# SB_schematic.net
KiCad netlist of a schematic drawn in Altium Designer
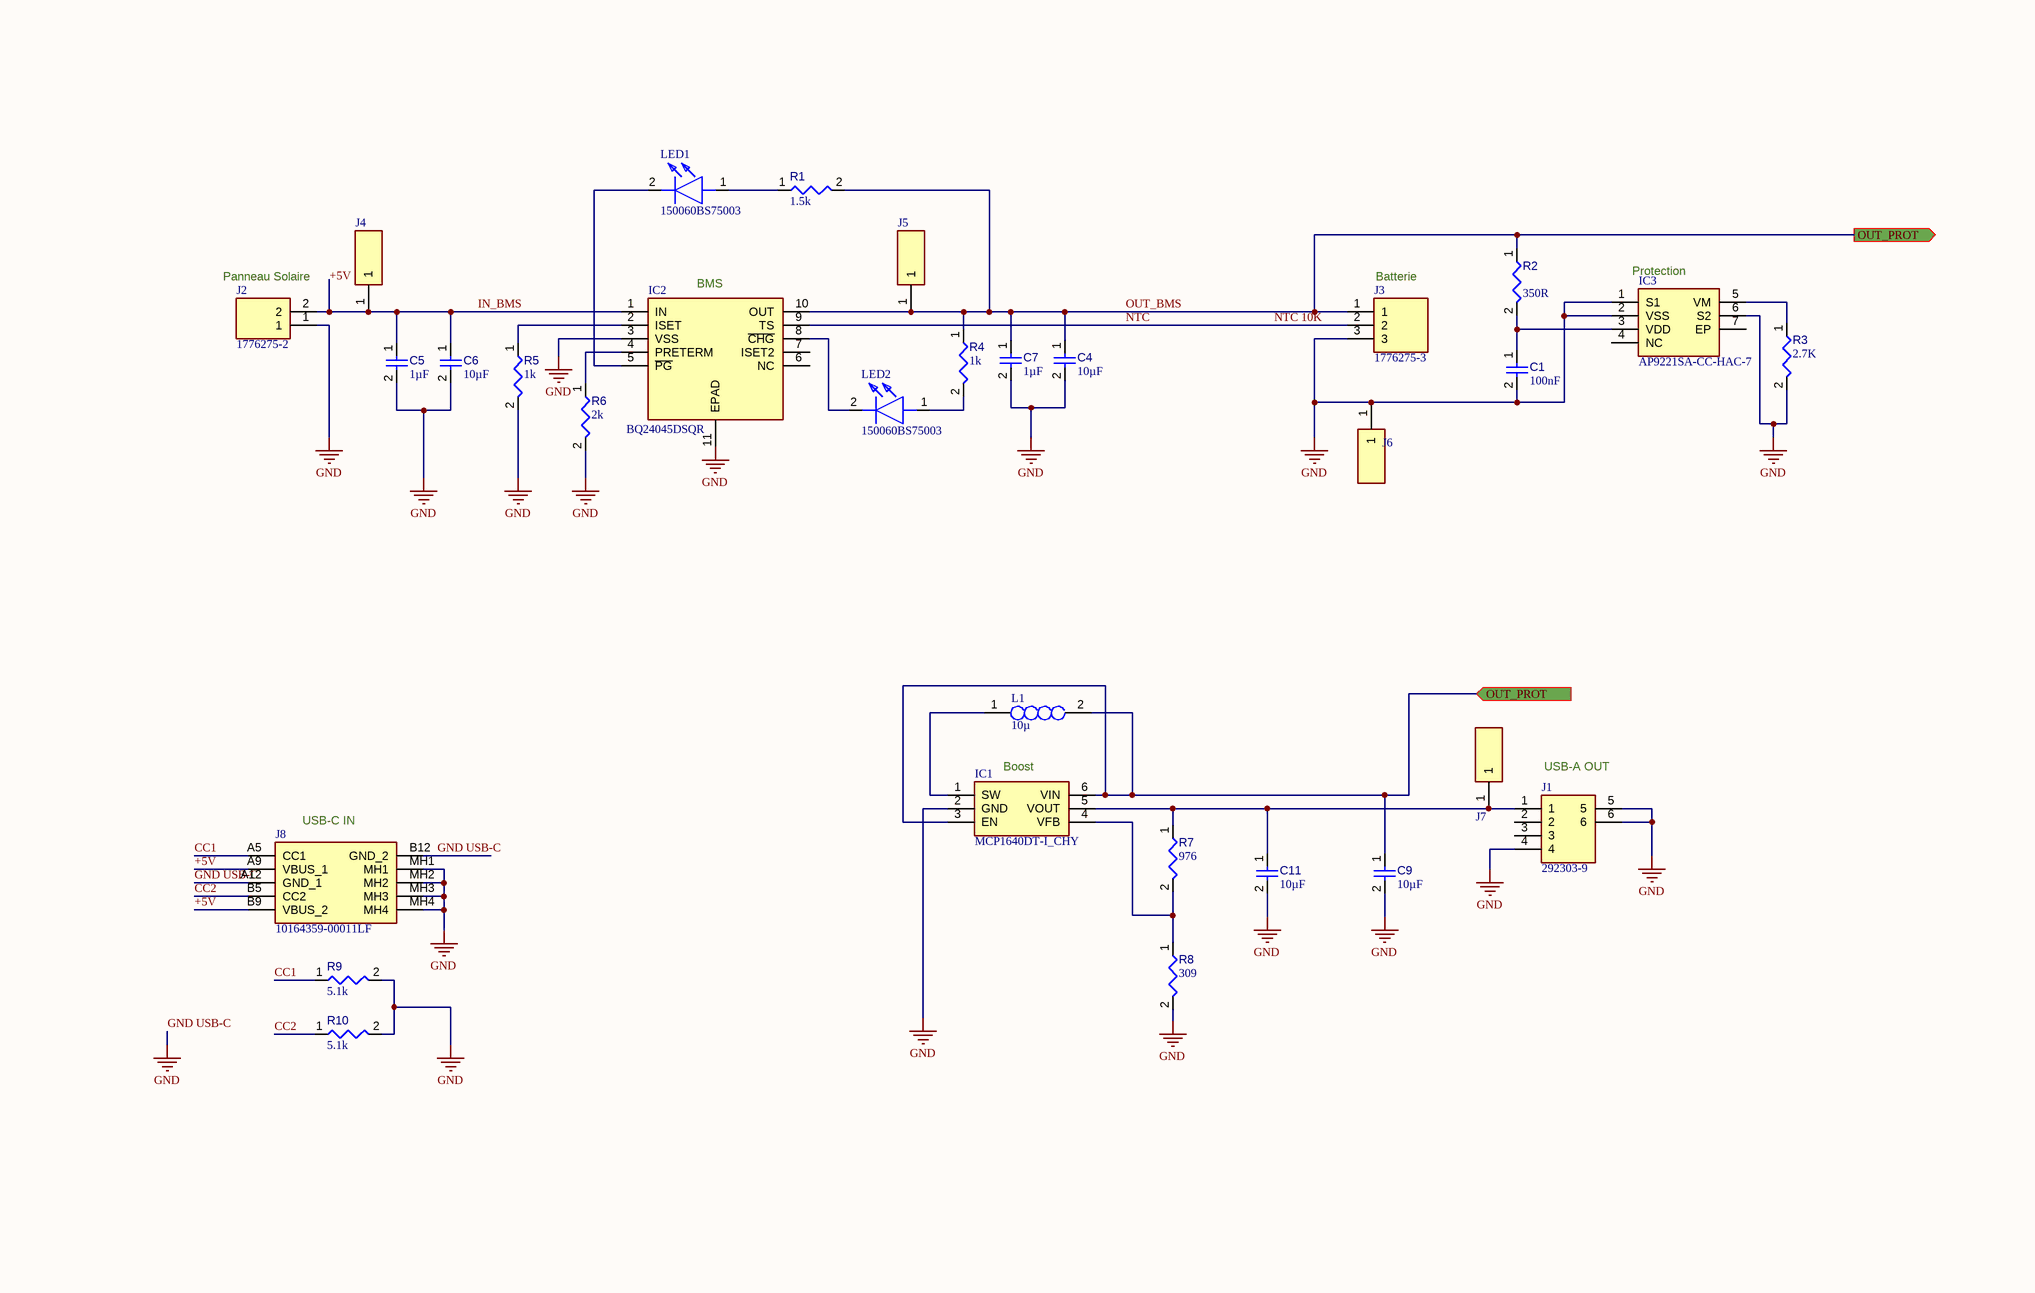
[diagram p0: SB_schematic.SchDoc]

(export (version "E")
  (design (tool "Eeschema 10.0.6"))
  (components
    (comp (ref "C1")
      (value "100nF")
      (footprint "CAPC1608X90X40LL10T20")
      (description "Chip Capacitor, 1 uF, +/- 10%, 25 V, 0603 (1608 Metric)")
      (fields (field (name "TOLERANCE") "10%") (field (name "Comment") "Capacitor 100 nF"))
      (libsource (lib "Haute Ecole de La Province de Liège") (part "CAP-NP-2"))
    )
    (comp (ref "C4")
      (value "10µF")
      (footprint "CAPC1608X90X40LL10T20")
      (description "Chip Capacitor, 1 uF, +/- 10%, 25 V, 0603 (1608 Metric)")
      (fields (field (name "TOLERANCE") "10%") (field (name "Comment") "Capacitor 10 uF"))
      (libsource (lib "Haute Ecole de La Province de Liège") (part "CAP-NP-2"))
    )
    (comp (ref "C5")
      (value "1µF")
      (footprint "CAPC1608X90X40LL10T20")
      (description "Chip Capacitor, 1 uF, +/- 10%, 25 V, 0603 (1608 Metric)")
      (fields (field (name "TOLERANCE") "10%") (field (name "Comment") "Capacitor 1 uF +/- 10% 25 V 0603"))
      (libsource (lib "Haute Ecole de La Province de Liège") (part "CAP-NP-2"))
    )
    (comp (ref "C6")
      (value "10µF")
      (footprint "CAPC1608X90X40LL10T20")
      (description "Chip Capacitor, 10 uF,")
      (fields (field (name "TOLERANCE") "10%") (field (name "Comment") "Capacitor 10 uF"))
      (libsource (lib "Haute Ecole de La Province de Liège") (part "CAP-NP-2"))
    )
    (comp (ref "C7")
      (value "1µF")
      (footprint "CAPC1608X90X40LL10T20")
      (description "Chip Capacitor, 1 uF, +/- 10%, 25 V, 0603 (1608 Metric)")
      (fields (field (name "TOLERANCE") "10%") (field (name "Comment") "Capacitor 1 uF +/- 10% 25 V 0603"))
      (libsource (lib "Haute Ecole de La Province de Liège") (part "CAP-NP-2"))
    )
    (comp (ref "C9")
      (value "10µF")
      (footprint "CAPC1608X90X40LL10T20")
      (description "Chip Capacitor, 1 uF, +/- 10%, 25 V, 0603 (1608 Metric)")
      (fields (field (name "TOLERANCE") "10%") (field (name "Comment") "Capacitor 10 uF"))
      (libsource (lib "Haute Ecole de La Province de Liège") (part "CAP-NP-2"))
    )
    (comp (ref "C11")
      (value "10µF")
      (footprint "CAPC1608X90X40LL10T20")
      (description "Chip Capacitor, 1 uF, +/- 10%, 25 V, 0603 (1608 Metric)")
      (fields (field (name "TOLERANCE") "10%") (field (name "Comment") "Capacitor 10 uF"))
      (libsource (lib "Haute Ecole de La Province de Liège") (part "CAP-NP-2"))
    )
    (comp (ref "IC1")
      (value "MCP1640DT-I_CHY")
      (footprint "SamacSys:SOT95P270X145-6N")
      (description "Integrated Circuit")
      (fields
        (field (name "MANUFACTURER_PART_NUMBER") "MCP1640DT-I/CHY")
        (field (name "MOUSER PART NUMBER") "579-MCP1640DT-I/CHY")
      )
      (libsource (lib "*") (part "MCP1640DT-I_CHY"))
    )
    (comp (ref "IC2")
      (value "BQ24045DSQR")
      (footprint "SamacSys:SON40P200X200X80-11N")
      (description "Integrated Circuit")
      (fields (field (name "MOUSER PART NUMBER") "595-BQ24045DSQR"))
      (libsource (lib "*") (part "BQ24045DSQR"))
    )
    (comp (ref "IC3")
      (value "AP9221SA-CC-HAC-7")
      (footprint "SamacSys:AP9221SACCHAC7")
      (description "Integrated Circuit")
      (fields (field (name "MOUSER PART NUMBER") "621-AP9221SA-CCHAC-7"))
      (libsource (lib "*") (part "AP9221SA-CC-HAC-7"))
    )
    (comp (ref "J1")
      (value "292303-9")
      (footprint "SamacSys:2923039")
      (description "Connector")
      (fields (field (name "MOUSER PART NUMBER") "571-292303-9"))
      (libsource (lib "*") (part "292303-9"))
    )
    (comp (ref "J2")
      (value "1776275-2")
      (footprint "SamacSys:17762752")
      (description "Connector")
      (fields (field (name "MOUSER PART NUMBER") "571-1776275-2"))
      (libsource (lib "*") (part "1776275-2"))
    )
    (comp (ref "J3")
      (value "1776275-3")
      (footprint "SamacSys:17762753")
      (description "Connector")
      (fields (field (name "MOUSER PART NUMBER") "571-1776275-3"))
      (libsource (lib "*") (part "1776275-3"))
    )
    (comp (ref "J4")
      (value "050_LT_B2")
      (footprint "SamacSys:050LTB2")
      (description "Connector")
      (fields (field (name "MANUFACTURER_PART_NUMBER") "050/LT/B2"))
      (libsource (lib "*") (part "050_LT_B2"))
    )
    (comp (ref "J5")
      (value "050_LT_B2")
      (footprint "SamacSys:050LTB2")
      (description "Connector")
      (fields (field (name "MANUFACTURER_PART_NUMBER") "050/LT/B2"))
      (libsource (lib "*") (part "050_LT_B2"))
    )
    (comp (ref "J6")
      (value "050_LT_B2")
      (footprint "SamacSys:050LTB2")
      (description "Connector")
      (fields (field (name "MANUFACTURER_PART_NUMBER") "050/LT/B2"))
      (libsource (lib "") (part "050_LT_B2_1"))
    )
    (comp (ref "J7")
      (value "050_LT_B2")
      (footprint "SamacSys:050LTB2")
      (description "Connector")
      (fields (field (name "MANUFACTURER_PART_NUMBER") "050/LT/B2"))
      (libsource (lib "*") (part "050_LT_B2"))
    )
    (comp (ref "J8")
      (value "10164359-00011LF")
      (footprint "SamacSys:1016435900011LF")
      (description "Connector")
      (fields (field (name "MOUSER PART NUMBER") "649-10164359-00011LF"))
      (libsource (lib "*") (part "10164359-00011LF"))
    )
    (comp (ref "L1")
      (value "10µ")
      (footprint "SamacSys:74477710")
      (description "Inductor")
      (fields
        (field (name "MANUFACTURER_PART_NUMBER") "74477710")
        (field (name "MOUSER PART NUMBER") "710-74477710")
      )
      (libsource (lib "*") (part "74477710"))
    )
    (comp (ref "LED1")
      (value "150060BS75003")
      (footprint "SamacSys:150060BS75003")
      (description "LED")
      (fields (field (name "MOUSER PART NUMBER") "710-150060BS75003"))
      (libsource (lib "*") (part "150060BS75003"))
    )
    (comp (ref "LED2")
      (value "150060BS75003")
      (footprint "SamacSys:150060BS75003")
      (description "LED")
      (fields (field (name "MOUSER PART NUMBER") "710-150060BS75003"))
      (libsource (lib "*") (part "150060BS75003"))
    )
    (comp (ref "R1")
      (value "1.5k")
      (footprint "RESC0603(1608)_L")
      (description "Chip Resistor, 120 Ohms, +/-5 %, 0.1 W, -55 to 155 degC, 0603")
      (fields (field (name "POWER") "100mW") (field (name "TOLERANCE") "5%"))
      (libsource (lib "Haute Ecole de La Province de Liège") (part "RES-2"))
    )
    (comp (ref "R2")
      (value "350R")
      (footprint "RESC0603(1608)_L")
      (description "Chip Resistor, 120 Ohms, +/-5 %, 0.1 W, -55 to 155 degC, 0603")
      (fields (field (name "POWER") "100mW") (field (name "TOLERANCE") "5%"))
      (libsource (lib "Haute Ecole de La Province de Liège") (part "RES-2"))
    )
    (comp (ref "R3")
      (value "2.7K")
      (footprint "RESC0603(1608)_L")
      (description "Chip Resistor, 120 Ohms, +/-5 %, 0.1 W, -55 to 155 degC, 0603")
      (fields (field (name "POWER") "100mW") (field (name "TOLERANCE") "5%"))
      (libsource (lib "Haute Ecole de La Province de Liège") (part "RES-2"))
    )
    (comp (ref "R4")
      (value "1k")
      (footprint "RESC0603(1608)_L")
      (description "Chip Resistor, 120 Ohms, +/-5 %, 0.1 W, -55 to 155 degC, 0603")
      (fields (field (name "POWER") "100mW") (field (name "TOLERANCE") "5%"))
      (libsource (lib "Haute Ecole de La Province de Liège") (part "RES-2"))
    )
    (comp (ref "R5")
      (value "1k")
      (footprint "RESC0603(1608)_L")
      (description "Chip Resistor, 120 Ohms, +/-5 %, 0.1 W, -55 to 155 degC, 0603")
      (fields (field (name "POWER") "100mW") (field (name "TOLERANCE") "5%"))
      (libsource (lib "Haute Ecole de La Province de Liège") (part "RES-2"))
    )
    (comp (ref "R6")
      (value "2k")
      (footprint "RESC0603(1608)_L")
      (description "Chip Resistor, 120 Ohms, +/-5 %, 0.1 W, -55 to 155 degC, 0603")
      (fields (field (name "POWER") "100mW") (field (name "TOLERANCE") "5%"))
      (libsource (lib "Haute Ecole de La Province de Liège") (part "RES-2"))
    )
    (comp (ref "R7")
      (value "976")
      (footprint "RESC0603(1608)_L")
      (description "Chip Resistor, 120 Ohms, +/-5 %, 0.1 W, -55 to 155 degC, 0603")
      (fields (field (name "POWER") "100mW") (field (name "TOLERANCE") "5%"))
      (libsource (lib "Haute Ecole de La Province de Liège") (part "RES-2"))
    )
    (comp (ref "R8")
      (value "309")
      (footprint "RESC0603(1608)_L")
      (description "Chip Resistor, 120 Ohms, +/-5 %, 0.1 W, -55 to 155 degC, 0603")
      (fields (field (name "POWER") "100mW") (field (name "TOLERANCE") "5%"))
      (libsource (lib "Haute Ecole de La Province de Liège") (part "RES-2"))
    )
    (comp (ref "R9")
      (value "5.1k")
      (footprint "RESC0603(1608)_L")
      (description "Chip Resistor, 120 Ohms, +/-5 %, 0.1 W, -55 to 155 degC, 0603")
      (fields (field (name "POWER") "100mW") (field (name "TOLERANCE") "5%"))
      (libsource (lib "Haute Ecole de La Province de Liège") (part "RES-2"))
    )
    (comp (ref "R10")
      (value "5.1k")
      (footprint "RESC0603(1608)_L")
      (description "Chip Resistor, 120 Ohms, +/-5 %, 0.1 W, -55 to 155 degC, 0603")
      (fields (field (name "POWER") "100mW") (field (name "TOLERANCE") "5%"))
      (libsource (lib "Haute Ecole de La Province de Liège") (part "RES-2"))
    )
  )
  (nets
    (net (code "1") (name "/+5V") (class "Default")
      (node (ref "C5") (pin "1") (pinfunction "1_1") (pintype "passive"))
      (node (ref "C6") (pin "1") (pinfunction "1_1") (pintype "passive"))
      (node (ref "IC2") (pin "1") (pinfunction "IN_1") (pintype "passive"))
      (node (ref "J2") (pin "2") (pinfunction "2_2") (pintype "passive"))
      (node (ref "J4") (pin "1") (pinfunction "1_1") (pintype "passive"))
      (node (ref "J8") (pin "A9") (pinfunction "VBUS_1_A9") (pintype "passive"))
      (node (ref "J8") (pin "B9") (pinfunction "VBUS_2_B9") (pintype "passive"))
    )
    (net (code "2") (name "/CC1") (class "Default")
      (node (ref "J8") (pin "A5") (pinfunction "CC1_A5") (pintype "passive"))
      (node (ref "R9") (pin "1") (pinfunction "1_1") (pintype "passive"))
    )
    (net (code "3") (name "/CC2") (class "Default")
      (node (ref "J8") (pin "B5") (pinfunction "CC2_B5") (pintype "passive"))
      (node (ref "R10") (pin "1") (pinfunction "1_1") (pintype "passive"))
    )
    (net (code "4") (name "/NTC") (class "Default")
      (node (ref "IC2") (pin "9") (pinfunction "TS_9") (pintype "passive"))
      (node (ref "J3") (pin "2") (pinfunction "2_2") (pintype "passive"))
    )
    (net (code "5") (name "/OUT_BMS") (class "Default")
      (node (ref "C4") (pin "1") (pinfunction "1_1") (pintype "passive"))
      (node (ref "C7") (pin "1") (pinfunction "1_1") (pintype "passive"))
      (node (ref "C9") (pin "1") (pinfunction "1_1") (pintype "passive"))
      (node (ref "IC1") (pin "3") (pinfunction "EN_3") (pintype "passive"))
      (node (ref "IC1") (pin "6") (pinfunction "VIN_6") (pintype "passive"))
      (node (ref "IC2") (pin "10") (pinfunction "OUT_10") (pintype "passive"))
      (node (ref "J3") (pin "1") (pinfunction "1_1") (pintype "passive"))
      (node (ref "J5") (pin "1") (pinfunction "1_1") (pintype "passive"))
      (node (ref "L1") (pin "2") (pinfunction "2_2") (pintype "passive"))
      (node (ref "R1") (pin "2") (pinfunction "2_2") (pintype "passive"))
      (node (ref "R2") (pin "1") (pinfunction "1_1") (pintype "passive"))
      (node (ref "R4") (pin "1") (pinfunction "1_1") (pintype "passive"))
    )
    (net (code "6") (name "GND") (class "Default")
      (node (ref "C1") (pin "2") (pinfunction "2_2") (pintype "passive"))
      (node (ref "C11") (pin "2") (pinfunction "2_2") (pintype "passive"))
      (node (ref "C4") (pin "2") (pinfunction "2_2") (pintype "passive"))
      (node (ref "C5") (pin "2") (pinfunction "2_2") (pintype "passive"))
      (node (ref "C6") (pin "2") (pinfunction "2_2") (pintype "passive"))
      (node (ref "C7") (pin "2") (pinfunction "2_2") (pintype "passive"))
      (node (ref "C9") (pin "2") (pinfunction "2_2") (pintype "passive"))
      (node (ref "IC1") (pin "2") (pinfunction "GND_2") (pintype "passive"))
      (node (ref "IC2") (pin "11") (pinfunction "EPAD_11") (pintype "passive"))
      (node (ref "IC2") (pin "3") (pinfunction "VSS_3") (pintype "passive"))
      (node (ref "IC3") (pin "1") (pinfunction "S1_1") (pintype "passive"))
      (node (ref "IC3") (pin "2") (pinfunction "VSS_2") (pintype "passive"))
      (node (ref "IC3") (pin "6") (pinfunction "S2_6") (pintype "passive"))
      (node (ref "J1") (pin "4") (pinfunction "4_4") (pintype "passive"))
      (node (ref "J1") (pin "5") (pinfunction "5_5") (pintype "passive"))
      (node (ref "J1") (pin "6") (pinfunction "6_6") (pintype "passive"))
      (node (ref "J2") (pin "1") (pinfunction "1_1") (pintype "passive"))
      (node (ref "J3") (pin "3") (pinfunction "3_3") (pintype "passive"))
      (node (ref "J6") (pin "1") (pinfunction "1_1") (pintype "passive"))
      (node (ref "J8") (pin "A12") (pinfunction "GND_1_A12") (pintype "passive"))
      (node (ref "J8") (pin "B12") (pinfunction "GND_2_B12") (pintype "passive"))
      (node (ref "J8") (pin "MH1") (pinfunction "MH1_MH1") (pintype "passive"))
      (node (ref "J8") (pin "MH2") (pinfunction "MH2_MH2") (pintype "passive"))
      (node (ref "J8") (pin "MH3") (pinfunction "MH3_MH3") (pintype "passive"))
      (node (ref "J8") (pin "MH4") (pinfunction "MH4_MH4") (pintype "passive"))
      (node (ref "R10") (pin "2") (pinfunction "2_2") (pintype "passive"))
      (node (ref "R3") (pin "2") (pinfunction "2_2") (pintype "passive"))
      (node (ref "R5") (pin "2") (pinfunction "2_2") (pintype "passive"))
      (node (ref "R6") (pin "2") (pinfunction "2_2") (pintype "passive"))
      (node (ref "R8") (pin "2") (pinfunction "2_2") (pintype "passive"))
      (node (ref "R9") (pin "2") (pinfunction "2_2") (pintype "passive"))
    )
    (net (code "7") (name "Net-(IC1-SW)") (class "Default")
      (node (ref "IC1") (pin "1") (pinfunction "SW_1") (pintype "passive"))
      (node (ref "L1") (pin "1") (pinfunction "1_1") (pintype "passive"))
    )
    (net (code "8") (name "Net-(IC1-VFB)") (class "Default")
      (node (ref "IC1") (pin "4") (pinfunction "VFB_4") (pintype "passive"))
      (node (ref "R7") (pin "2") (pinfunction "2_2") (pintype "passive"))
      (node (ref "R8") (pin "1") (pinfunction "1_1") (pintype "passive"))
    )
    (net (code "9") (name "Net-(IC1-VOUT)") (class "Default")
      (node (ref "C11") (pin "1") (pinfunction "1_1") (pintype "passive"))
      (node (ref "IC1") (pin "5") (pinfunction "VOUT_5") (pintype "passive"))
      (node (ref "J1") (pin "1") (pinfunction "1_1") (pintype "passive"))
      (node (ref "J7") (pin "1") (pinfunction "1_1") (pintype "passive"))
      (node (ref "R7") (pin "1") (pinfunction "1_1") (pintype "passive"))
    )
    (net (code "10") (name "Net-(IC2-ISET)") (class "Default")
      (node (ref "IC2") (pin "2") (pinfunction "ISET_2") (pintype "passive"))
      (node (ref "R5") (pin "1") (pinfunction "1_1") (pintype "passive"))
    )
    (net (code "11") (name "Net-(IC2-PRETERM)") (class "Default")
      (node (ref "IC2") (pin "4") (pinfunction "PRETERM_4") (pintype "passive"))
      (node (ref "R6") (pin "1") (pinfunction "1_1") (pintype "passive"))
    )
    (net (code "12") (name "Net-(IC2-~{CHG})") (class "Default")
      (node (ref "IC2") (pin "8") (pinfunction "~{CHG}_8") (pintype "passive"))
      (node (ref "LED2") (pin "2") (pinfunction "K_2") (pintype "passive"))
    )
    (net (code "13") (name "Net-(IC2-~{PG})") (class "Default")
      (node (ref "IC2") (pin "5") (pinfunction "~{PG}_5") (pintype "passive"))
      (node (ref "LED1") (pin "2") (pinfunction "K_2") (pintype "passive"))
    )
    (net (code "14") (name "Net-(IC3-VDD)") (class "Default")
      (node (ref "C1") (pin "1") (pinfunction "1_1") (pintype "passive"))
      (node (ref "IC3") (pin "3") (pinfunction "VDD_3") (pintype "passive"))
      (node (ref "R2") (pin "2") (pinfunction "2_2") (pintype "passive"))
    )
    (net (code "15") (name "Net-(IC3-VM)") (class "Default")
      (node (ref "IC3") (pin "5") (pinfunction "VM_5") (pintype "passive"))
      (node (ref "R3") (pin "1") (pinfunction "1_1") (pintype "passive"))
    )
    (net (code "16") (name "Net-(LED1-A)") (class "Default")
      (node (ref "LED1") (pin "1") (pinfunction "A_1") (pintype "passive"))
      (node (ref "R1") (pin "1") (pinfunction "1_1") (pintype "passive"))
    )
    (net (code "17") (name "Net-(LED2-A)") (class "Default")
      (node (ref "LED2") (pin "1") (pinfunction "A_1") (pintype "passive"))
      (node (ref "R4") (pin "2") (pinfunction "2_2") (pintype "passive"))
    )
    (net (code "18") (name "unconnected-(IC2-ISET2-Pad7)") (class "Default")
      (node (ref "IC2") (pin "7") (pinfunction "ISET2_7") (pintype "passive"))
    )
    (net (code "19") (name "unconnected-(IC2-NC-Pad6)") (class "Default")
      (node (ref "IC2") (pin "6") (pinfunction "NC_6") (pintype "passive"))
    )
    (net (code "20") (name "unconnected-(IC3-EP-Pad7)") (class "Default")
      (node (ref "IC3") (pin "7") (pinfunction "EP_7") (pintype "passive"))
    )
    (net (code "21") (name "unconnected-(IC3-NC-Pad4)") (class "Default")
      (node (ref "IC3") (pin "4") (pinfunction "NC_4") (pintype "passive"))
    )
    (net (code "22") (name "unconnected-(J1-Pad2)") (class "Default")
      (node (ref "J1") (pin "2") (pinfunction "2_2") (pintype "passive"))
    )
    (net (code "23") (name "unconnected-(J1-Pad3)") (class "Default")
      (node (ref "J1") (pin "3") (pinfunction "3_3") (pintype "passive"))
    )
  )
)
